# module_v1.net
KiCad netlist of a schematic drawn in EAGLE
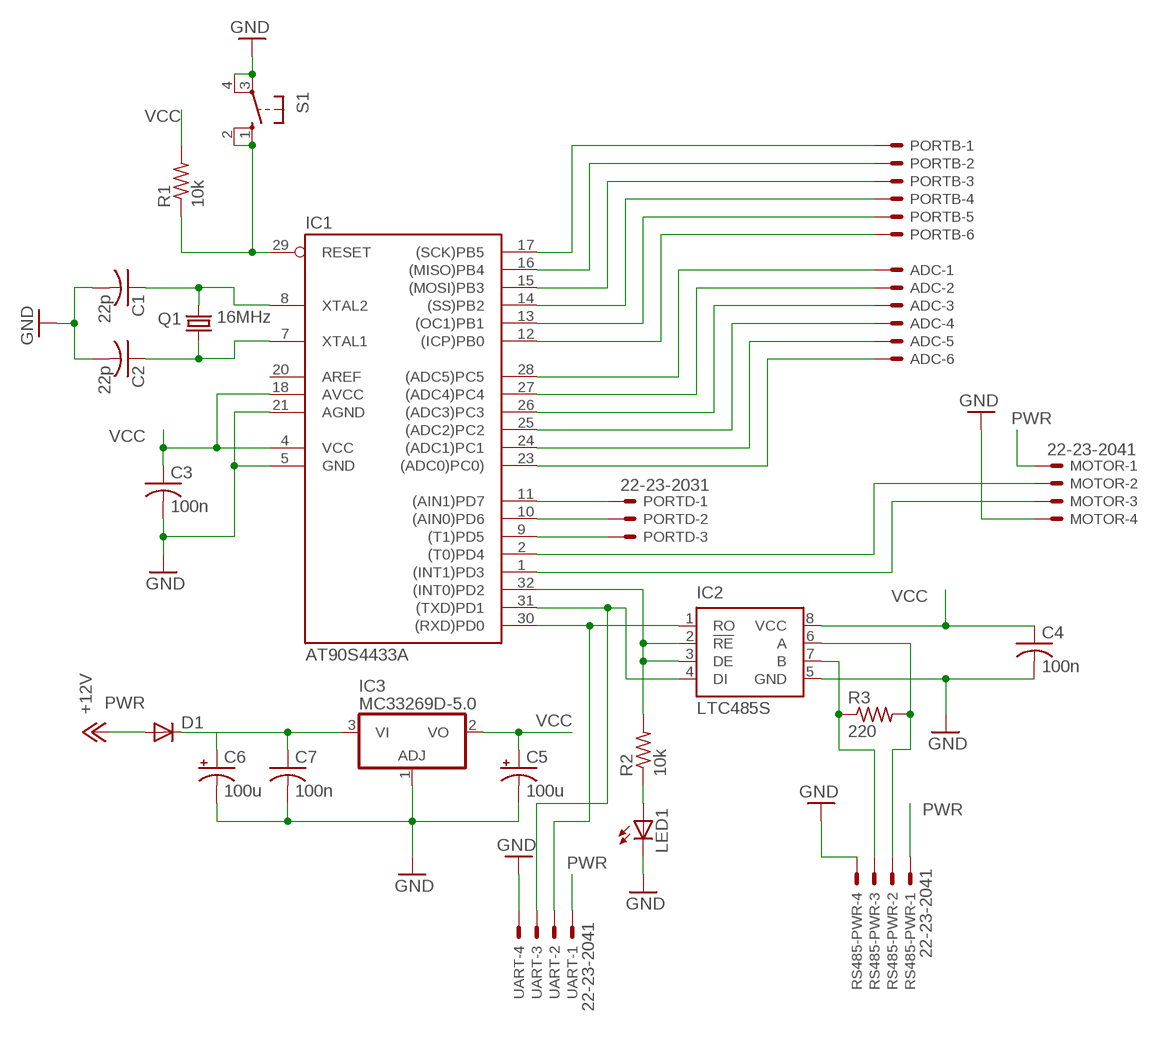
[diagram p0: schematic, sheet 1]

(export (version "E")
  (design (tool "Eeschema 10.0.6"))
  (components
    (comp (ref "ADC")
      (value "22-23-2061")
      (footprint "eagle-import:22-23-2061")
      (fields (field (name "MF") "MOLEX"))
      (libsource (lib "eagle-import") (part "22-23-2061"))
    )
    (comp (ref "C1")
      (value "22p")
      (footprint "eagle-import:C0805")
      (libsource (lib "eagle-import") (part "C-USC0805"))
    )
    (comp (ref "C2")
      (value "22p")
      (footprint "eagle-import:C0805")
      (libsource (lib "eagle-import") (part "C-USC0805"))
    )
    (comp (ref "C3")
      (value "100n")
      (footprint "eagle-import:C0805")
      (libsource (lib "eagle-import") (part "C-USC0805"))
    )
    (comp (ref "C4")
      (value "100n")
      (footprint "eagle-import:C0805")
      (libsource (lib "eagle-import") (part "C-USC0805"))
    )
    (comp (ref "C5")
      (value "100u")
      (footprint "eagle-import:PANASONIC_D")
      (libsource (lib "eagle-import") (part "CPOL-USD"))
    )
    (comp (ref "C6")
      (value "100u")
      (footprint "eagle-import:PANASONIC_D")
      (libsource (lib "eagle-import") (part "CPOL-USD"))
    )
    (comp (ref "C7")
      (value "100n")
      (footprint "eagle-import:C0805")
      (libsource (lib "eagle-import") (part "C-USC0805"))
    )
    (comp (ref "D1")
      (value "DIODE-SMB")
      (footprint "eagle-import:SMB")
      (libsource (lib "eagle-import") (part "DIODE-SMB"))
    )
    (comp (ref "IC1")
      (value "AT90S4433A")
      (footprint "eagle-import:TQFP32-08")
      (libsource (lib "eagle-import") (part "AT90S4433A"))
    )
    (comp (ref "IC2")
      (value "LTC485S")
      (footprint "eagle-import:SOIC8")
      (libsource (lib "eagle-import") (part "LTC485S"))
    )
    (comp (ref "IC3")
      (value "MC33269D-5.0")
      (footprint "eagle-import:DPACK")
      (libsource (lib "eagle-import") (part "MC33269?D-5.0"))
    )
    (comp (ref "LED1")
      (value "LEDCHIP-LED0805")
      (footprint "eagle-import:CHIP-LED0805")
      (libsource (lib "eagle-import") (part "LEDCHIP-LED0805"))
    )
    (comp (ref "MOTOR")
      (value "22-23-2041")
      (footprint "eagle-import:22-23-2041")
      (fields (field (name "MF") "MOLEX"))
      (libsource (lib "eagle-import") (part "22-23-2041"))
    )
    (comp (ref "PORTB")
      (value "22-23-2061")
      (footprint "eagle-import:22-23-2061")
      (fields (field (name "MF") "MOLEX"))
      (libsource (lib "eagle-import") (part "22-23-2061"))
    )
    (comp (ref "PORTD")
      (value "22-23-2031")
      (footprint "eagle-import:22-23-2031")
      (fields (field (name "MF") "MOLEX"))
      (libsource (lib "eagle-import") (part "22-23-2031"))
    )
    (comp (ref "Q1")
      (value "16MHz")
      (footprint "eagle-import:HC49_S")
      (libsource (lib "eagle-import") (part "CRYSTALHC49S"))
    )
    (comp (ref "R1")
      (value "10k")
      (footprint "eagle-import:R0805")
      (libsource (lib "eagle-import") (part "R-US_R0805"))
    )
    (comp (ref "R2")
      (value "10k")
      (footprint "eagle-import:R0805")
      (libsource (lib "eagle-import") (part "R-US_R0805"))
    )
    (comp (ref "R3")
      (value "220")
      (footprint "eagle-import:R0805")
      (libsource (lib "eagle-import") (part "R-US_R0805"))
    )
    (comp (ref "RS485-PWR")
      (value "22-23-2041")
      (footprint "eagle-import:22-23-2041")
      (fields (field (name "MF") "MOLEX"))
      (libsource (lib "eagle-import") (part "22-23-2041"))
    )
    (comp (ref "S1")
      (value "10-XX")
      (footprint "eagle-import:B3F-10XX")
      (fields (field (name "MPN") "B3F-1000"))
      (libsource (lib "eagle-import") (part "10-XX"))
    )
    (comp (ref "UART")
      (value "22-23-2041")
      (footprint "eagle-import:22-23-2041")
      (fields (field (name "MF") "MOLEX"))
      (libsource (lib "eagle-import") (part "22-23-2041"))
    )
  )
  (nets
    (net (code "1") (name "+12V") (class "Default")
      (node (ref "D1") (pin "A") (pinfunction "A_A") (pintype "passive"))
      (node (ref "MOTOR") (pin "1") (pinfunction "S_1") (pintype "passive"))
      (node (ref "RS485-PWR") (pin "1") (pinfunction "S_1") (pintype "passive"))
      (node (ref "UART") (pin "1") (pinfunction "S_1") (pintype "passive"))
    )
    (net (code "2") (name "/VCC") (class "Default")
      (node (ref "C3") (pin "1") (pinfunction "1_1") (pintype "passive"))
      (node (ref "C4") (pin "1") (pinfunction "1_1") (pintype "passive"))
      (node (ref "C5") (pin "+") (pinfunction "+_+") (pintype "passive"))
      (node (ref "IC1") (pin "18") (pinfunction "AVCC_18") (pintype "power_in"))
      (node (ref "IC1") (pin "4") (pinfunction "VCC_4") (pintype "power_in"))
      (node (ref "IC2") (pin "8") (pinfunction "VCC_8") (pintype "input"))
      (node (ref "IC3") (pin "2") (pinfunction "VO_2") (pintype "passive"))
      (node (ref "R1") (pin "2") (pinfunction "2_2") (pintype "passive"))
    )
    (net (code "3") (name "GND") (class "Default")
      (node (ref "C1") (pin "2") (pinfunction "2_2") (pintype "passive"))
      (node (ref "C2") (pin "2") (pinfunction "2_2") (pintype "passive"))
      (node (ref "C3") (pin "2") (pinfunction "2_2") (pintype "passive"))
      (node (ref "C4") (pin "2") (pinfunction "2_2") (pintype "passive"))
      (node (ref "C5") (pin "-") (pinfunction "-_-") (pintype "passive"))
      (node (ref "C6") (pin "-") (pinfunction "-_-") (pintype "passive"))
      (node (ref "C7") (pin "2") (pinfunction "2_2") (pintype "passive"))
      (node (ref "IC1") (pin "21") (pinfunction "AGND_21") (pintype "power_in"))
      (node (ref "IC1") (pin "5") (pinfunction "GND_5") (pintype "power_in"))
      (node (ref "IC2") (pin "5") (pinfunction "GND_5") (pintype "input"))
      (node (ref "IC3") (pin "1") (pinfunction "ADJ_1") (pintype "input"))
      (node (ref "LED1") (pin "C") (pinfunction "C_C") (pintype "passive"))
      (node (ref "MOTOR") (pin "4") (pinfunction "S_4") (pintype "passive"))
      (node (ref "RS485-PWR") (pin "4") (pinfunction "S_4") (pintype "passive"))
      (node (ref "S1") (pin "3") (pinfunction "P_3") (pintype "passive"))
      (node (ref "S1") (pin "4") (pinfunction "P1_4") (pintype "passive"))
      (node (ref "UART") (pin "4") (pinfunction "S_4") (pintype "passive"))
    )
    (net (code "4") (name "Net-(ADCA-S)") (class "Default")
      (node (ref "ADC") (pin "1") (pinfunction "S_1") (pintype "passive"))
      (node (ref "IC1") (pin "28") (pinfunction "(ADC5)PC5_28") (pintype "bidirectional"))
    )
    (net (code "5") (name "Net-(ADCB-S)") (class "Default")
      (node (ref "ADC") (pin "2") (pinfunction "S_2") (pintype "passive"))
      (node (ref "IC1") (pin "27") (pinfunction "(ADC4)PC4_27") (pintype "bidirectional"))
    )
    (net (code "6") (name "Net-(ADCC-S)") (class "Default")
      (node (ref "ADC") (pin "3") (pinfunction "S_3") (pintype "passive"))
      (node (ref "IC1") (pin "26") (pinfunction "(ADC3)PC3_26") (pintype "bidirectional"))
    )
    (net (code "7") (name "Net-(ADCD-S)") (class "Default")
      (node (ref "ADC") (pin "4") (pinfunction "S_4") (pintype "passive"))
      (node (ref "IC1") (pin "25") (pinfunction "(ADC2)PC2_25") (pintype "bidirectional"))
    )
    (net (code "8") (name "Net-(ADCE-S)") (class "Default")
      (node (ref "ADC") (pin "5") (pinfunction "S_5") (pintype "passive"))
      (node (ref "IC1") (pin "24") (pinfunction "(ADC1)PC1_24") (pintype "bidirectional"))
    )
    (net (code "9") (name "Net-(ADCF-S)") (class "Default")
      (node (ref "ADC") (pin "6") (pinfunction "S_6") (pintype "passive"))
      (node (ref "IC1") (pin "23") (pinfunction "(ADC0)PC0)_23") (pintype "bidirectional"))
    )
    (net (code "10") (name "Net-(IC1-(AIN0)PD6)") (class "Default")
      (node (ref "IC1") (pin "10") (pinfunction "(AIN0)PD6_10") (pintype "bidirectional"))
      (node (ref "PORTD") (pin "2") (pinfunction "S_2") (pintype "passive"))
    )
    (net (code "11") (name "Net-(IC1-(AIN1)PD7)") (class "Default")
      (node (ref "IC1") (pin "11") (pinfunction "(AIN1)PD7_11") (pintype "bidirectional"))
      (node (ref "PORTD") (pin "1") (pinfunction "S_1") (pintype "passive"))
    )
    (net (code "12") (name "Net-(IC1-(ICP)PB0)") (class "Default")
      (node (ref "IC1") (pin "12") (pinfunction "(ICP)PB0_12") (pintype "bidirectional"))
      (node (ref "PORTB") (pin "6") (pinfunction "S_6") (pintype "passive"))
    )
    (net (code "13") (name "Net-(IC1-(INT0)PD2)") (class "Default")
      (node (ref "IC1") (pin "32") (pinfunction "(INT0)PD2_32") (pintype "bidirectional"))
      (node (ref "IC2") (pin "2") (pinfunction "~{RE}_2") (pintype "input"))
      (node (ref "IC2") (pin "3") (pinfunction "DE_3") (pintype "input"))
      (node (ref "R2") (pin "2") (pinfunction "2_2") (pintype "passive"))
    )
    (net (code "14") (name "Net-(IC1-(INT1)PD3)") (class "Default")
      (node (ref "IC1") (pin "1") (pinfunction "(INT1)PD3_1") (pintype "bidirectional"))
      (node (ref "MOTOR") (pin "3") (pinfunction "S_3") (pintype "passive"))
    )
    (net (code "15") (name "Net-(IC1-(MISO)PB4)") (class "Default")
      (node (ref "IC1") (pin "16") (pinfunction "(MISO)PB4_16") (pintype "bidirectional"))
      (node (ref "PORTB") (pin "2") (pinfunction "S_2") (pintype "passive"))
    )
    (net (code "16") (name "Net-(IC1-(MOSI)PB3)") (class "Default")
      (node (ref "IC1") (pin "15") (pinfunction "(MOSI)PB3_15") (pintype "bidirectional"))
      (node (ref "PORTB") (pin "3") (pinfunction "S_3") (pintype "passive"))
    )
    (net (code "17") (name "Net-(IC1-(OC1)PB1)") (class "Default")
      (node (ref "IC1") (pin "13") (pinfunction "(OC1)PB1_13") (pintype "bidirectional"))
      (node (ref "PORTB") (pin "5") (pinfunction "S_5") (pintype "passive"))
    )
    (net (code "18") (name "Net-(IC1-(RXD)PD0)") (class "Default")
      (node (ref "IC1") (pin "30") (pinfunction "(RXD)PD0_30") (pintype "bidirectional"))
      (node (ref "IC2") (pin "1") (pinfunction "RO_1") (pintype "output"))
      (node (ref "UART") (pin "2") (pinfunction "S_2") (pintype "passive"))
    )
    (net (code "19") (name "Net-(IC1-(SCK)PB5)") (class "Default")
      (node (ref "IC1") (pin "17") (pinfunction "(SCK)PB5_17") (pintype "bidirectional"))
      (node (ref "PORTB") (pin "1") (pinfunction "S_1") (pintype "passive"))
    )
    (net (code "20") (name "Net-(IC1-(SS)PB2)") (class "Default")
      (node (ref "IC1") (pin "14") (pinfunction "(SS)PB2_14") (pintype "bidirectional"))
      (node (ref "PORTB") (pin "4") (pinfunction "S_4") (pintype "passive"))
    )
    (net (code "21") (name "Net-(IC1-(T0)PD4)") (class "Default")
      (node (ref "IC1") (pin "2") (pinfunction "(T0)PD4_2") (pintype "bidirectional"))
      (node (ref "MOTOR") (pin "2") (pinfunction "S_2") (pintype "passive"))
    )
    (net (code "22") (name "Net-(IC1-(T1)PD5)") (class "Default")
      (node (ref "IC1") (pin "9") (pinfunction "(T1)PD5_9") (pintype "bidirectional"))
      (node (ref "PORTD") (pin "3") (pinfunction "S_3") (pintype "passive"))
    )
    (net (code "23") (name "Net-(IC1-(TXD)PD1)") (class "Default")
      (node (ref "IC1") (pin "31") (pinfunction "(TXD)PD1_31") (pintype "bidirectional"))
      (node (ref "IC2") (pin "4") (pinfunction "DI_4") (pintype "input"))
      (node (ref "UART") (pin "3") (pinfunction "S_3") (pintype "passive"))
    )
    (net (code "24") (name "Net-(IC1-RESET)") (class "Default")
      (node (ref "IC1") (pin "29") (pinfunction "RESET_29") (pintype "input"))
      (node (ref "R1") (pin "1") (pinfunction "1_1") (pintype "passive"))
      (node (ref "S1") (pin "1") (pinfunction "S_1") (pintype "passive"))
      (node (ref "S1") (pin "2") (pinfunction "S1_2") (pintype "passive"))
    )
    (net (code "25") (name "Net-(IC1-XTAL1)") (class "Default")
      (node (ref "C2") (pin "1") (pinfunction "1_1") (pintype "passive"))
      (node (ref "IC1") (pin "7") (pinfunction "XTAL1_7") (pintype "bidirectional"))
      (node (ref "Q1") (pin "1") (pinfunction "1_1") (pintype "passive"))
    )
    (net (code "26") (name "Net-(IC1-XTAL2)") (class "Default")
      (node (ref "C1") (pin "1") (pinfunction "1_1") (pintype "passive"))
      (node (ref "IC1") (pin "8") (pinfunction "XTAL2_8") (pintype "bidirectional"))
      (node (ref "Q1") (pin "2") (pinfunction "2_2") (pintype "passive"))
    )
    (net (code "27") (name "Net-(IC2-A)") (class "Default")
      (node (ref "IC2") (pin "6") (pinfunction "A_6") (pintype "bidirectional"))
      (node (ref "R3") (pin "2") (pinfunction "2_2") (pintype "passive"))
      (node (ref "RS485-PWR") (pin "2") (pinfunction "S_2") (pintype "passive"))
    )
    (net (code "28") (name "Net-(IC2-B)") (class "Default")
      (node (ref "IC2") (pin "7") (pinfunction "B_7") (pintype "bidirectional"))
      (node (ref "R3") (pin "1") (pinfunction "1_1") (pintype "passive"))
      (node (ref "RS485-PWR") (pin "3") (pinfunction "S_3") (pintype "passive"))
    )
    (net (code "29") (name "Net-(IC3-VI)") (class "Default")
      (node (ref "C6") (pin "+") (pinfunction "+_+") (pintype "passive"))
      (node (ref "C7") (pin "1") (pinfunction "1_1") (pintype "passive"))
      (node (ref "D1") (pin "C") (pinfunction "C_C") (pintype "passive"))
      (node (ref "IC3") (pin "3") (pinfunction "VI_3") (pintype "input"))
    )
    (net (code "30") (name "Net-(LED1-PadA)") (class "Default")
      (node (ref "LED1") (pin "A") (pinfunction "A_A") (pintype "passive"))
      (node (ref "R2") (pin "1") (pinfunction "1_1") (pintype "passive"))
    )
    (net (code "31") (name "unconnected-(IC1-AREF-Pad20)") (class "Default")
      (node (ref "IC1") (pin "20") (pinfunction "AREF_20") (pintype "passive"))
    )
  )
)
